# MemoryBoard_AT25DFxxx.net
KiCad netlist of a schematic drawn in Altium Designer
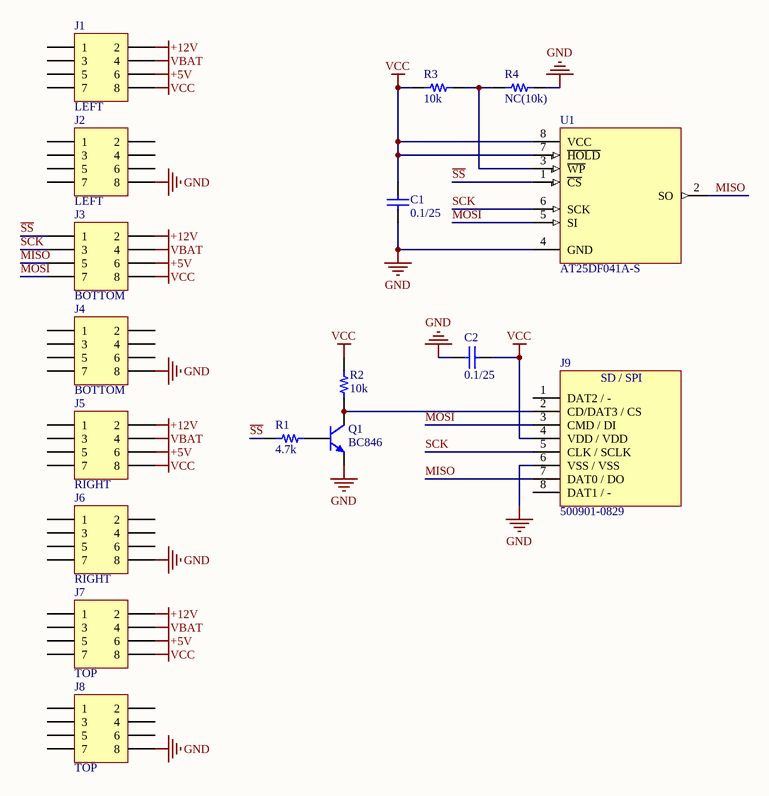
[diagram p0: MemoryBoard_AT25DFxxx.SchDoc]

(export (version "E")
  (design (tool "Eeschema 10.0.6"))
  (components
    (comp (ref "C1")
      (value "0.1/25")
      (footprint "CAP0402")
      (description "Ceramic chip capacitor 0402")
      (fields
        (field (name "PARTNUMBER") "CAP0402")
        (field (name "VOLTAGE") "25")
        (field (name "AUTHOR") "oiezhov")
      )
      (libsource (lib "Library") (part "Capacitor"))
    )
    (comp (ref "C2")
      (value "0.1/25")
      (footprint "CAP0402")
      (description "Ceramic chip capacitor 0402")
      (fields
        (field (name "PARTNUMBER") "CAP0402")
        (field (name "VOLTAGE") "25")
        (field (name "AUTHOR") "oiezhov")
      )
      (libsource (lib "Library") (part "Capacitor"))
    )
    (comp (ref "J1")
      (value "LEFT")
      (footprint "PBDM-8")
      (description "2x4-pin header, pitch 2.54 mm")
      (fields (field (name "PARTNUMBER") "PBDM-8") (field (name "AUTHOR") "oiezhov"))
      (libsource (lib "Library") (part "8-pin dual row connector"))
    )
    (comp (ref "J2")
      (value "LEFT")
      (footprint "PBDM-8")
      (description "2x4-pin header, pitch 2.54 mm")
      (fields (field (name "PARTNUMBER") "PBDM-8") (field (name "AUTHOR") "oiezhov"))
      (libsource (lib "Library") (part "8-pin dual row connector"))
    )
    (comp (ref "J3")
      (value "BOTTOM")
      (footprint "PBDM-8")
      (description "2x4-pin header, pitch 2.54 mm")
      (fields (field (name "PARTNUMBER") "PBDM-8") (field (name "AUTHOR") "oiezhov"))
      (libsource (lib "Library") (part "8-pin dual row connector"))
    )
    (comp (ref "J4")
      (value "BOTTOM")
      (footprint "PBDM-8")
      (description "2x4-pin header, pitch 2.54 mm")
      (fields (field (name "PARTNUMBER") "PBDM-8") (field (name "AUTHOR") "oiezhov"))
      (libsource (lib "Library") (part "8-pin dual row connector"))
    )
    (comp (ref "J5")
      (value "RIGHT")
      (footprint "PBDM-8")
      (description "2x4-pin header, pitch 2.54 mm")
      (fields (field (name "PARTNUMBER") "PBDM-8") (field (name "AUTHOR") "oiezhov"))
      (libsource (lib "Library") (part "8-pin dual row connector"))
    )
    (comp (ref "J6")
      (value "RIGHT")
      (footprint "PBDM-8")
      (description "2x4-pin header, pitch 2.54 mm")
      (fields (field (name "PARTNUMBER") "PBDM-8") (field (name "AUTHOR") "oiezhov"))
      (libsource (lib "Library") (part "8-pin dual row connector"))
    )
    (comp (ref "J7")
      (value "TOP")
      (footprint "PBDM-8")
      (description "2x4-pin header, pitch 2.54 mm")
      (fields (field (name "PARTNUMBER") "PBDM-8") (field (name "AUTHOR") "oiezhov"))
      (libsource (lib "Library") (part "8-pin dual row connector"))
    )
    (comp (ref "J8")
      (value "TOP")
      (footprint "PBDM-8")
      (description "2x4-pin header, pitch 2.54 mm")
      (fields (field (name "PARTNUMBER") "PBDM-8") (field (name "AUTHOR") "oiezhov"))
      (libsource (lib "Library") (part "8-pin dual row connector"))
    )
    (comp (ref "J9")
      (value "500901-0829")
      (footprint "MOLEX 500901-0829")
      (description "Micro SD card connector")
      (fields (field (name "AUTHOR") "oiezhov"))
      (libsource (lib "Library") (part "microSD card connector"))
    )
    (comp (ref "Q1")
      (value "BC846")
      (footprint "SOT23")
      (description "NPN Silicon AF Transistor")
      (fields (field (name "AUTHOR") "oiezhov"))
      (libsource (lib "Library") (part "NPN Transistor (B-E-C)"))
    )
    (comp (ref "R1")
      (value "4.7k")
      (footprint "RES0402")
      (description "Ceramic chip resistor")
      (fields (field (name "PARTNUMBER") "RES0402") (field (name "AUTHOR") "oiezhov"))
      (libsource (lib "Library") (part "Resistor"))
    )
    (comp (ref "R2")
      (value "10k")
      (footprint "RES0402")
      (description "Ceramic chip resistor")
      (fields (field (name "PARTNUMBER") "RES0402") (field (name "AUTHOR") "oiezhov"))
      (libsource (lib "Library") (part "Resistor"))
    )
    (comp (ref "R3")
      (value "10k")
      (footprint "RES0402")
      (description "Ceramic chip resistor")
      (fields (field (name "PARTNUMBER") "RES0402") (field (name "AUTHOR") "oiezhov"))
      (libsource (lib "Library") (part "Resistor"))
    )
    (comp (ref "R4")
      (value "NC(10k)")
      (footprint "RES0402")
      (description "Ceramic chip resistor")
      (fields (field (name "PARTNUMBER") "RES0402") (field (name "AUTHOR") "oiezhov"))
      (libsource (lib "Library") (part "Resistor"))
    )
    (comp (ref "U1")
      (value "AT25DF041A-S")
      (footprint "SO8-208")
      (description "4-Mbit Serial Peripheral Interface Serial Flash Memory")
      (fields (field (name "AUTHOR") "oiezhov"))
      (libsource (lib "Library") (part "8-pin SPI flash"))
    )
  )
  (nets
    (net (code "1") (name "+5V") (class "Default")
      (node (ref "J1") (pin "6") (pinfunction "6_6") (pintype "passive"))
      (node (ref "J3") (pin "6") (pinfunction "6_6") (pintype "passive"))
      (node (ref "J5") (pin "6") (pinfunction "6_6") (pintype "passive"))
      (node (ref "J7") (pin "6") (pinfunction "6_6") (pintype "passive"))
    )
    (net (code "2") (name "+12V") (class "Default")
      (node (ref "J1") (pin "2") (pinfunction "2_2") (pintype "passive"))
      (node (ref "J3") (pin "2") (pinfunction "2_2") (pintype "passive"))
      (node (ref "J5") (pin "2") (pinfunction "2_2") (pintype "passive"))
      (node (ref "J7") (pin "2") (pinfunction "2_2") (pintype "passive"))
    )
    (net (code "3") (name "/MISO") (class "Default")
      (node (ref "J3") (pin "5") (pinfunction "5_5") (pintype "passive"))
      (node (ref "J9") (pin "7") (pinfunction "DAT0_/_DO_7") (pintype "passive"))
      (node (ref "U1") (pin "2") (pinfunction "SO_2") (pintype "output"))
    )
    (net (code "4") (name "/MOSI") (class "Default")
      (node (ref "J3") (pin "7") (pinfunction "7_7") (pintype "passive"))
      (node (ref "J9") (pin "3") (pinfunction "CMD_/_DI_3") (pintype "passive"))
      (node (ref "U1") (pin "5") (pinfunction "SI_5") (pintype "input"))
    )
    (net (code "5") (name "/SCK") (class "Default")
      (node (ref "J3") (pin "3") (pinfunction "3_3") (pintype "passive"))
      (node (ref "J9") (pin "5") (pinfunction "CLK_/_SCLK_5") (pintype "passive"))
      (node (ref "U1") (pin "6") (pinfunction "SCK_6") (pintype "input"))
    )
    (net (code "6") (name "/~{SS}") (class "Default")
      (node (ref "J3") (pin "1") (pinfunction "1_1") (pintype "passive"))
      (node (ref "R1") (pin "1") (pinfunction "1_1") (pintype "passive"))
      (node (ref "U1") (pin "1") (pinfunction "~{CS}_1") (pintype "input"))
    )
    (net (code "7") (name "GND") (class "Default")
      (node (ref "C1") (pin "1") (pinfunction "1_1") (pintype "passive"))
      (node (ref "C2") (pin "2") (pinfunction "2_2") (pintype "passive"))
      (node (ref "J2") (pin "8") (pinfunction "8_8") (pintype "passive"))
      (node (ref "J4") (pin "8") (pinfunction "8_8") (pintype "passive"))
      (node (ref "J6") (pin "8") (pinfunction "8_8") (pintype "passive"))
      (node (ref "J8") (pin "8") (pinfunction "8_8") (pintype "passive"))
      (node (ref "J9") (pin "6") (pinfunction "VSS_/_VSS_6") (pintype "passive"))
      (node (ref "Q1") (pin "2") (pinfunction "2_2") (pintype "passive"))
      (node (ref "R4") (pin "2") (pinfunction "2_2") (pintype "passive"))
      (node (ref "U1") (pin "4") (pinfunction "GND_4") (pintype "power_in"))
    )
    (net (code "8") (name "Net-(J9-CD{slash}DAT3_{slash}_CS)") (class "Default")
      (node (ref "J9") (pin "2") (pinfunction "CD/DAT3_/_CS_2") (pintype "passive"))
      (node (ref "Q1") (pin "3") (pinfunction "3_3") (pintype "passive"))
      (node (ref "R2") (pin "2") (pinfunction "2_2") (pintype "passive"))
    )
    (net (code "9") (name "Net-(Q1-Pad1)") (class "Default")
      (node (ref "Q1") (pin "1") (pinfunction "1_1") (pintype "passive"))
      (node (ref "R1") (pin "2") (pinfunction "2_2") (pintype "passive"))
    )
    (net (code "10") (name "Net-(U1-~{WP})") (class "Default")
      (node (ref "R3") (pin "2") (pinfunction "2_2") (pintype "passive"))
      (node (ref "R4") (pin "1") (pinfunction "1_1") (pintype "passive"))
      (node (ref "U1") (pin "3") (pinfunction "~{WP}_3") (pintype "input"))
    )
    (net (code "11") (name "VBAT") (class "Default")
      (node (ref "J1") (pin "4") (pinfunction "4_4") (pintype "passive"))
      (node (ref "J3") (pin "4") (pinfunction "4_4") (pintype "passive"))
      (node (ref "J5") (pin "4") (pinfunction "4_4") (pintype "passive"))
      (node (ref "J7") (pin "4") (pinfunction "4_4") (pintype "passive"))
    )
    (net (code "12") (name "VCC") (class "Default")
      (node (ref "C1") (pin "2") (pinfunction "2_2") (pintype "passive"))
      (node (ref "C2") (pin "1") (pinfunction "1_1") (pintype "passive"))
      (node (ref "J1") (pin "8") (pinfunction "8_8") (pintype "passive"))
      (node (ref "J3") (pin "8") (pinfunction "8_8") (pintype "passive"))
      (node (ref "J5") (pin "8") (pinfunction "8_8") (pintype "passive"))
      (node (ref "J7") (pin "8") (pinfunction "8_8") (pintype "passive"))
      (node (ref "J9") (pin "4") (pinfunction "VDD_/_VDD_4") (pintype "passive"))
      (node (ref "R2") (pin "1") (pinfunction "1_1") (pintype "passive"))
      (node (ref "R3") (pin "1") (pinfunction "1_1") (pintype "passive"))
      (node (ref "U1") (pin "7") (pinfunction "~{HOLD}_7") (pintype "input"))
      (node (ref "U1") (pin "8") (pinfunction "VCC_8") (pintype "power_in"))
    )
    (net (code "13") (name "unconnected-(J1-Pad1)") (class "Default")
      (node (ref "J1") (pin "1") (pinfunction "1_1") (pintype "passive"))
    )
    (net (code "14") (name "unconnected-(J1-Pad3)") (class "Default")
      (node (ref "J1") (pin "3") (pinfunction "3_3") (pintype "passive"))
    )
    (net (code "15") (name "unconnected-(J1-Pad5)") (class "Default")
      (node (ref "J1") (pin "5") (pinfunction "5_5") (pintype "passive"))
    )
    (net (code "16") (name "unconnected-(J1-Pad7)") (class "Default")
      (node (ref "J1") (pin "7") (pinfunction "7_7") (pintype "passive"))
    )
    (net (code "17") (name "unconnected-(J2-Pad1)") (class "Default")
      (node (ref "J2") (pin "1") (pinfunction "1_1") (pintype "passive"))
    )
    (net (code "18") (name "unconnected-(J2-Pad2)") (class "Default")
      (node (ref "J2") (pin "2") (pinfunction "2_2") (pintype "passive"))
    )
    (net (code "19") (name "unconnected-(J2-Pad3)") (class "Default")
      (node (ref "J2") (pin "3") (pinfunction "3_3") (pintype "passive"))
    )
    (net (code "20") (name "unconnected-(J2-Pad4)") (class "Default")
      (node (ref "J2") (pin "4") (pinfunction "4_4") (pintype "passive"))
    )
    (net (code "21") (name "unconnected-(J2-Pad5)") (class "Default")
      (node (ref "J2") (pin "5") (pinfunction "5_5") (pintype "passive"))
    )
    (net (code "22") (name "unconnected-(J2-Pad6)") (class "Default")
      (node (ref "J2") (pin "6") (pinfunction "6_6") (pintype "passive"))
    )
    (net (code "23") (name "unconnected-(J2-Pad7)") (class "Default")
      (node (ref "J2") (pin "7") (pinfunction "7_7") (pintype "passive"))
    )
    (net (code "24") (name "unconnected-(J4-Pad1)") (class "Default")
      (node (ref "J4") (pin "1") (pinfunction "1_1") (pintype "passive"))
    )
    (net (code "25") (name "unconnected-(J4-Pad2)") (class "Default")
      (node (ref "J4") (pin "2") (pinfunction "2_2") (pintype "passive"))
    )
    (net (code "26") (name "unconnected-(J4-Pad3)") (class "Default")
      (node (ref "J4") (pin "3") (pinfunction "3_3") (pintype "passive"))
    )
    (net (code "27") (name "unconnected-(J4-Pad4)") (class "Default")
      (node (ref "J4") (pin "4") (pinfunction "4_4") (pintype "passive"))
    )
    (net (code "28") (name "unconnected-(J4-Pad5)") (class "Default")
      (node (ref "J4") (pin "5") (pinfunction "5_5") (pintype "passive"))
    )
    (net (code "29") (name "unconnected-(J4-Pad6)") (class "Default")
      (node (ref "J4") (pin "6") (pinfunction "6_6") (pintype "passive"))
    )
    (net (code "30") (name "unconnected-(J4-Pad7)") (class "Default")
      (node (ref "J4") (pin "7") (pinfunction "7_7") (pintype "passive"))
    )
    (net (code "31") (name "unconnected-(J5-Pad1)") (class "Default")
      (node (ref "J5") (pin "1") (pinfunction "1_1") (pintype "passive"))
    )
    (net (code "32") (name "unconnected-(J5-Pad3)") (class "Default")
      (node (ref "J5") (pin "3") (pinfunction "3_3") (pintype "passive"))
    )
    (net (code "33") (name "unconnected-(J5-Pad5)") (class "Default")
      (node (ref "J5") (pin "5") (pinfunction "5_5") (pintype "passive"))
    )
    (net (code "34") (name "unconnected-(J5-Pad7)") (class "Default")
      (node (ref "J5") (pin "7") (pinfunction "7_7") (pintype "passive"))
    )
    (net (code "35") (name "unconnected-(J6-Pad1)") (class "Default")
      (node (ref "J6") (pin "1") (pinfunction "1_1") (pintype "passive"))
    )
    (net (code "36") (name "unconnected-(J6-Pad2)") (class "Default")
      (node (ref "J6") (pin "2") (pinfunction "2_2") (pintype "passive"))
    )
    (net (code "37") (name "unconnected-(J6-Pad3)") (class "Default")
      (node (ref "J6") (pin "3") (pinfunction "3_3") (pintype "passive"))
    )
    (net (code "38") (name "unconnected-(J6-Pad4)") (class "Default")
      (node (ref "J6") (pin "4") (pinfunction "4_4") (pintype "passive"))
    )
    (net (code "39") (name "unconnected-(J6-Pad5)") (class "Default")
      (node (ref "J6") (pin "5") (pinfunction "5_5") (pintype "passive"))
    )
    (net (code "40") (name "unconnected-(J6-Pad6)") (class "Default")
      (node (ref "J6") (pin "6") (pinfunction "6_6") (pintype "passive"))
    )
    (net (code "41") (name "unconnected-(J6-Pad7)") (class "Default")
      (node (ref "J6") (pin "7") (pinfunction "7_7") (pintype "passive"))
    )
    (net (code "42") (name "unconnected-(J7-Pad1)") (class "Default")
      (node (ref "J7") (pin "1") (pinfunction "1_1") (pintype "passive"))
    )
    (net (code "43") (name "unconnected-(J7-Pad3)") (class "Default")
      (node (ref "J7") (pin "3") (pinfunction "3_3") (pintype "passive"))
    )
    (net (code "44") (name "unconnected-(J7-Pad5)") (class "Default")
      (node (ref "J7") (pin "5") (pinfunction "5_5") (pintype "passive"))
    )
    (net (code "45") (name "unconnected-(J7-Pad7)") (class "Default")
      (node (ref "J7") (pin "7") (pinfunction "7_7") (pintype "passive"))
    )
    (net (code "46") (name "unconnected-(J8-Pad1)") (class "Default")
      (node (ref "J8") (pin "1") (pinfunction "1_1") (pintype "passive"))
    )
    (net (code "47") (name "unconnected-(J8-Pad2)") (class "Default")
      (node (ref "J8") (pin "2") (pinfunction "2_2") (pintype "passive"))
    )
    (net (code "48") (name "unconnected-(J8-Pad3)") (class "Default")
      (node (ref "J8") (pin "3") (pinfunction "3_3") (pintype "passive"))
    )
    (net (code "49") (name "unconnected-(J8-Pad4)") (class "Default")
      (node (ref "J8") (pin "4") (pinfunction "4_4") (pintype "passive"))
    )
    (net (code "50") (name "unconnected-(J8-Pad5)") (class "Default")
      (node (ref "J8") (pin "5") (pinfunction "5_5") (pintype "passive"))
    )
    (net (code "51") (name "unconnected-(J8-Pad6)") (class "Default")
      (node (ref "J8") (pin "6") (pinfunction "6_6") (pintype "passive"))
    )
    (net (code "52") (name "unconnected-(J8-Pad7)") (class "Default")
      (node (ref "J8") (pin "7") (pinfunction "7_7") (pintype "passive"))
    )
    (net (code "53") (name "unconnected-(J9-DAT1_{slash}_--Pad8)") (class "Default")
      (node (ref "J9") (pin "8") (pinfunction "DAT1_/_-_8") (pintype "passive"))
    )
    (net (code "54") (name "unconnected-(J9-DAT2_{slash}_--Pad1)") (class "Default")
      (node (ref "J9") (pin "1") (pinfunction "DAT2_/_-_1") (pintype "passive"))
    )
  )
)
